# ProPrj_ArduinoUNoShield_ELE795_2026-08-0.net
KiCad netlist of a schematic drawn in EasyEDA Pro
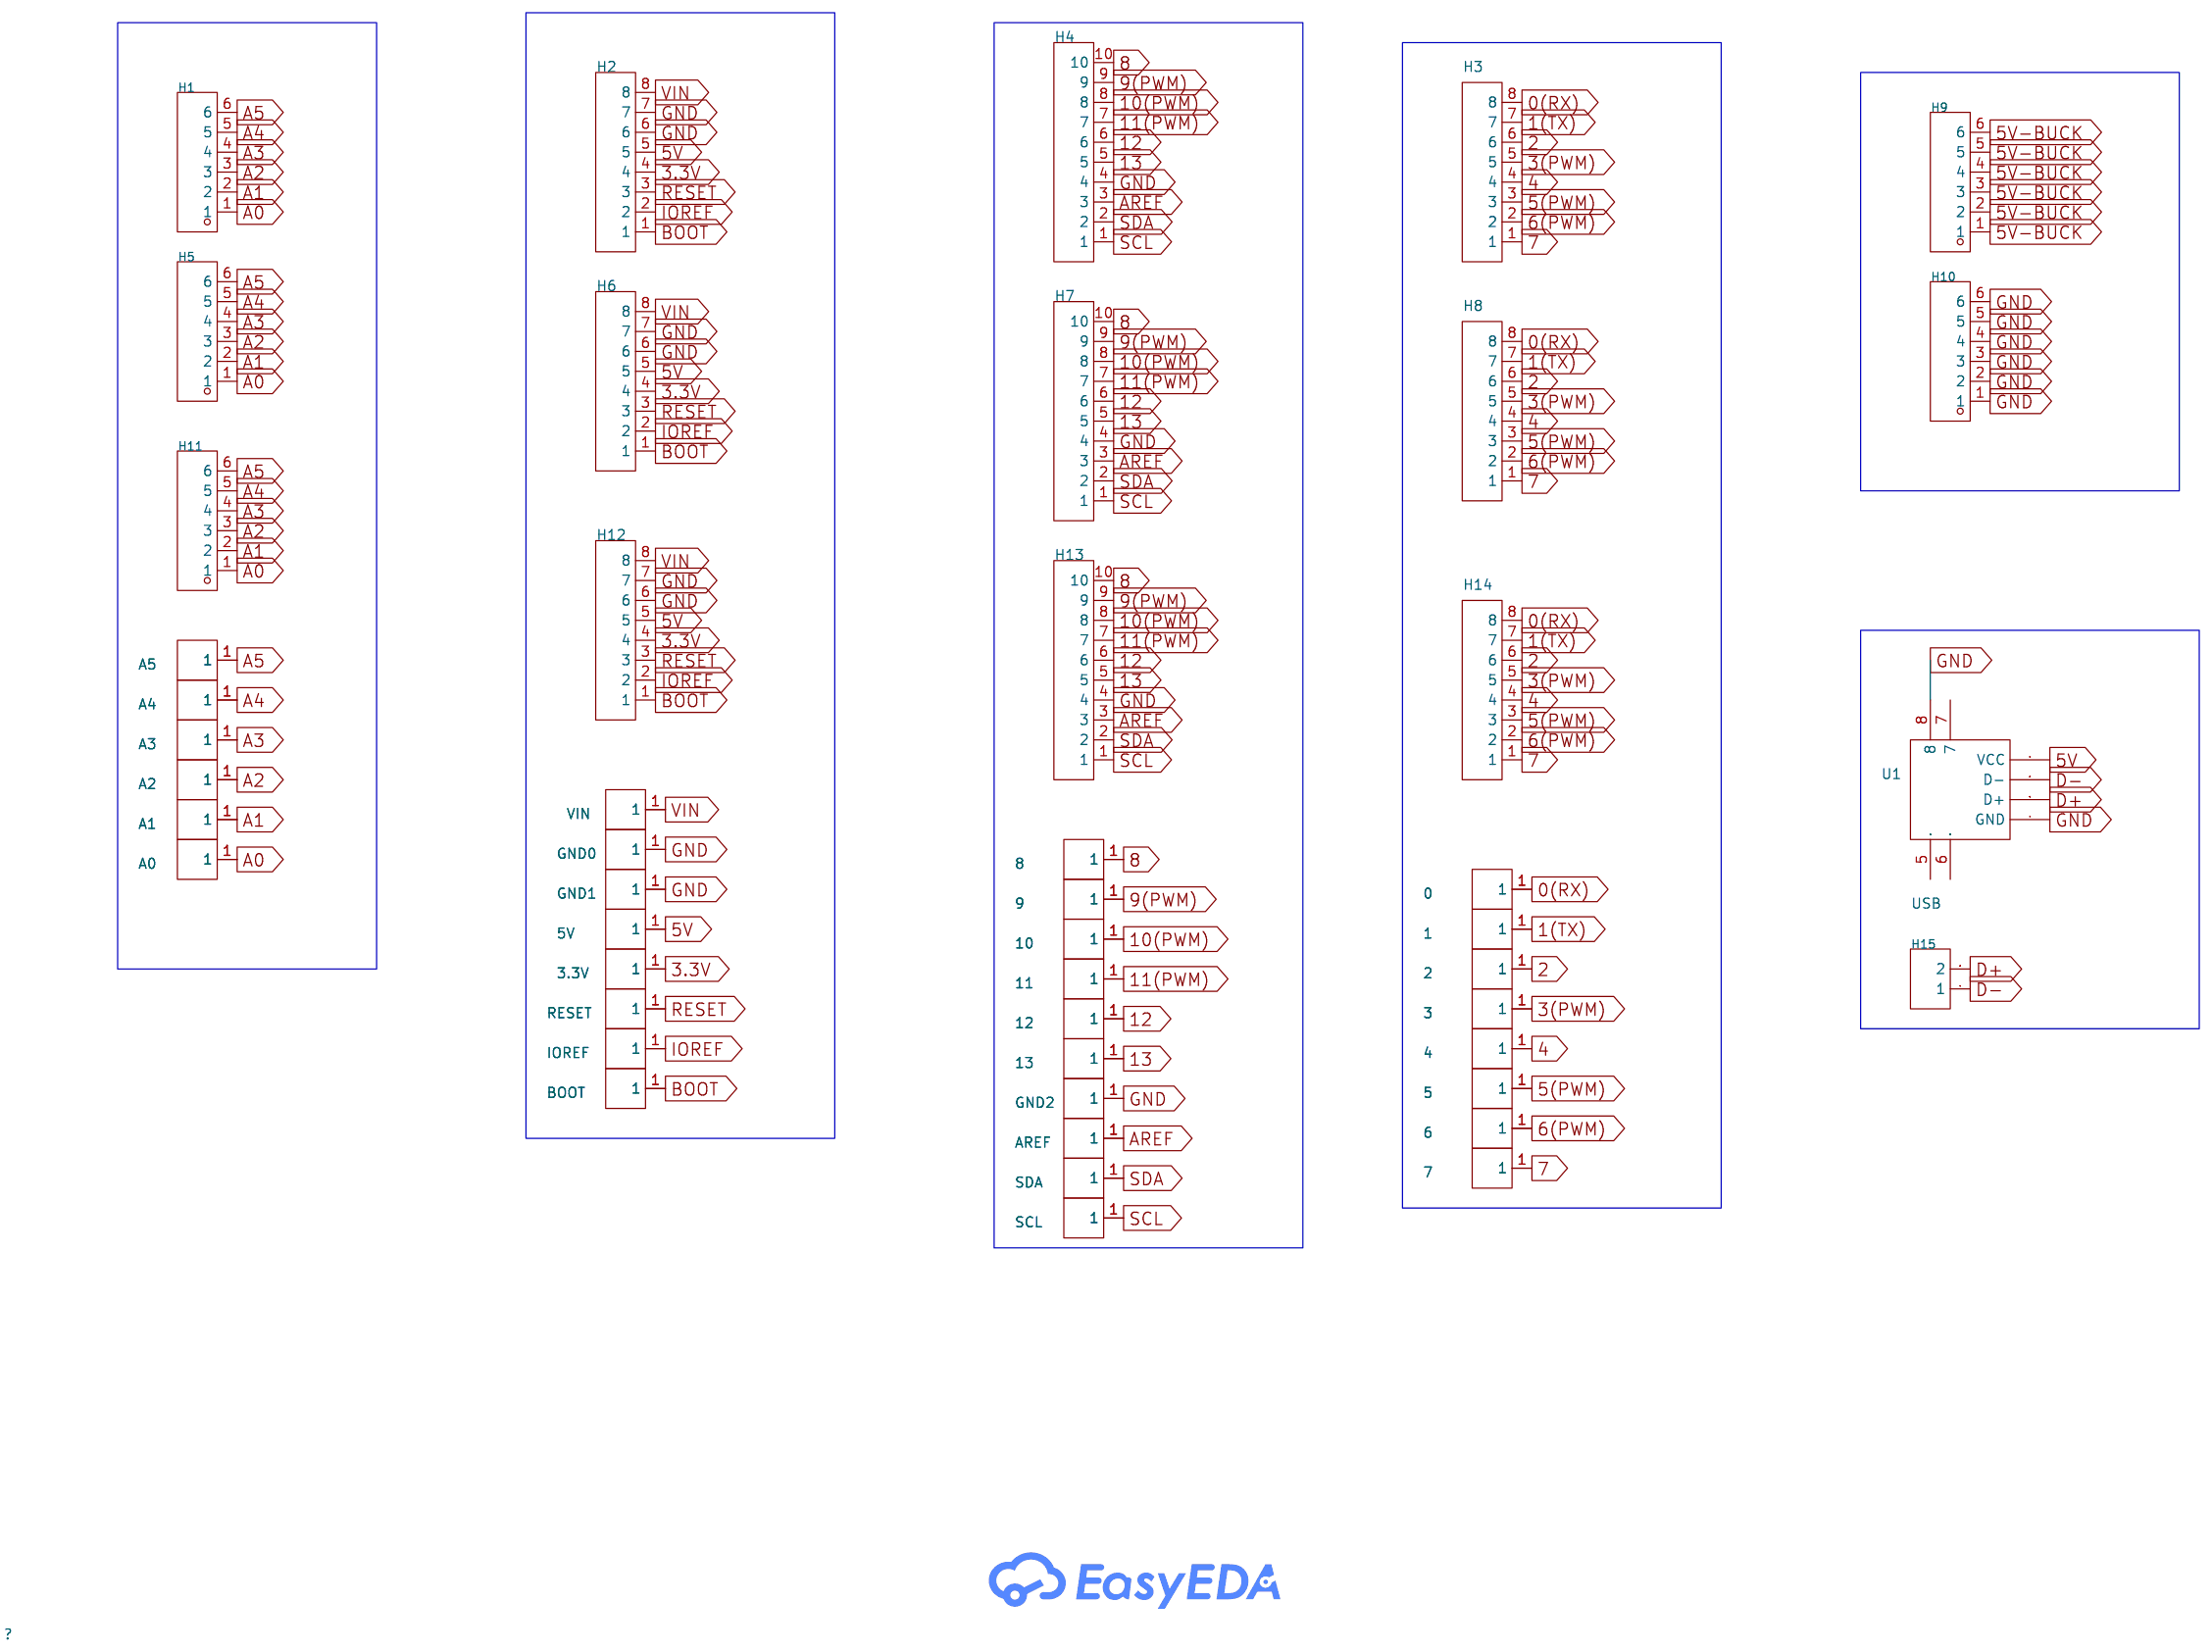
[diagram p0: schematic sheet]

(export (version "E")
  (design (tool "Eeschema 10.0.6"))
  (components
    (comp (ref "0")
      (value "5017")
      (footprint "easyedapro:CONN-SMD_5017")
      (libsource (lib "easyedapro") (part "5017_C9900015874"))
    )
    (comp (ref "1")
      (value "5017")
      (footprint "easyedapro:CONN-SMD_5017")
      (libsource (lib "easyedapro") (part "5017_C9900015874"))
    )
    (comp (ref "2")
      (value "5017")
      (footprint "easyedapro:CONN-SMD_5017")
      (libsource (lib "easyedapro") (part "5017_C9900015874"))
    )
    (comp (ref "3")
      (value "5017")
      (footprint "easyedapro:CONN-SMD_5017")
      (libsource (lib "easyedapro") (part "5017_C9900015874"))
    )
    (comp (ref "3.3V")
      (value "5017")
      (footprint "easyedapro:CONN-SMD_5017")
      (libsource (lib "easyedapro") (part "5017_C9900015874"))
    )
    (comp (ref "4")
      (value "5017")
      (footprint "easyedapro:CONN-SMD_5017")
      (libsource (lib "easyedapro") (part "5017_C9900015874"))
    )
    (comp (ref "5")
      (value "5017")
      (footprint "easyedapro:CONN-SMD_5017")
      (libsource (lib "easyedapro") (part "5017_C9900015874"))
    )
    (comp (ref "5V")
      (value "5017")
      (footprint "easyedapro:CONN-SMD_5017")
      (libsource (lib "easyedapro") (part "5017_C9900015874"))
    )
    (comp (ref "6")
      (value "5017")
      (footprint "easyedapro:CONN-SMD_5017")
      (libsource (lib "easyedapro") (part "5017_C9900015874"))
    )
    (comp (ref "7")
      (value "5017")
      (footprint "easyedapro:CONN-SMD_5017")
      (libsource (lib "easyedapro") (part "5017_C9900015874"))
    )
    (comp (ref "8")
      (value "5017")
      (footprint "easyedapro:CONN-SMD_5017")
      (libsource (lib "easyedapro") (part "5017_C9900015874"))
    )
    (comp (ref "9")
      (value "5017")
      (footprint "easyedapro:CONN-SMD_5017")
      (libsource (lib "easyedapro") (part "5017_C9900015874"))
    )
    (comp (ref "10")
      (value "5017")
      (footprint "easyedapro:CONN-SMD_5017")
      (libsource (lib "easyedapro") (part "5017_C9900015874"))
    )
    (comp (ref "11")
      (value "5017")
      (footprint "easyedapro:CONN-SMD_5017")
      (libsource (lib "easyedapro") (part "5017_C9900015874"))
    )
    (comp (ref "12")
      (value "5017")
      (footprint "easyedapro:CONN-SMD_5017")
      (libsource (lib "easyedapro") (part "5017_C9900015874"))
    )
    (comp (ref "13")
      (value "5017")
      (footprint "easyedapro:CONN-SMD_5017")
      (libsource (lib "easyedapro") (part "5017_C9900015874"))
    )
    (comp (ref "A0")
      (value "5017")
      (footprint "easyedapro:CONN-SMD_5017")
      (libsource (lib "easyedapro") (part "5017_C9900015874"))
    )
    (comp (ref "A1")
      (value "5017")
      (footprint "easyedapro:CONN-SMD_5017")
      (libsource (lib "easyedapro") (part "5017_C9900015874"))
    )
    (comp (ref "A2")
      (value "5017")
      (footprint "easyedapro:CONN-SMD_5017")
      (libsource (lib "easyedapro") (part "5017_C9900015874"))
    )
    (comp (ref "A3")
      (value "5017")
      (footprint "easyedapro:CONN-SMD_5017")
      (libsource (lib "easyedapro") (part "5017_C9900015874"))
    )
    (comp (ref "A4")
      (value "5017")
      (footprint "easyedapro:CONN-SMD_5017")
      (libsource (lib "easyedapro") (part "5017_C9900015874"))
    )
    (comp (ref "A5")
      (value "5017")
      (footprint "easyedapro:CONN-SMD_5017")
      (libsource (lib "easyedapro") (part "5017_C9900015874"))
    )
    (comp (ref "AREF")
      (value "5017")
      (footprint "easyedapro:CONN-SMD_5017")
      (libsource (lib "easyedapro") (part "5017_C9900015874"))
    )
    (comp (ref "BOOT")
      (value "5017")
      (footprint "easyedapro:CONN-SMD_5017")
      (libsource (lib "easyedapro") (part "5017_C9900015874"))
    )
    (comp (ref "GND0")
      (value "5017")
      (footprint "easyedapro:CONN-SMD_5017")
      (libsource (lib "easyedapro") (part "5017_C9900015874"))
    )
    (comp (ref "GND1")
      (value "5017")
      (footprint "easyedapro:CONN-SMD_5017")
      (libsource (lib "easyedapro") (part "5017_C9900015874"))
    )
    (comp (ref "GND2")
      (value "5017")
      (footprint "easyedapro:CONN-SMD_5017")
      (libsource (lib "easyedapro") (part "5017_C9900015874"))
    )
    (comp (ref "H1")
      (value "~")
      (footprint "easyedapro:HDR-TH_6P-P2.54-V-F")
      (libsource (lib "easyedapro") (part "Header-Female-2.54_1x6"))
    )
    (comp (ref "H2")
      (value "~")
      (footprint "easyedapro:HDR-TH_8P-P2.54-V-F-1")
      (libsource (lib "easyedapro") (part "Header-Female-2.54_1x8"))
    )
    (comp (ref "H3")
      (value "~")
      (footprint "easyedapro:HDR-TH_8P-P2.54-V-F-1")
      (libsource (lib "easyedapro") (part "Header-Female-2.54_1x8"))
    )
    (comp (ref "H4")
      (value "~")
      (footprint "easyedapro:HDR-TH_10P-P2.54-V-F")
      (libsource (lib "easyedapro") (part "X5511FV-10-C70D30-1000"))
    )
    (comp (ref "H5")
      (value "~")
      (footprint "easyedapro:HDR-TH_6P-P2.54-V-F")
      (libsource (lib "easyedapro") (part "Header-Female-2.54_1x6"))
    )
    (comp (ref "H6")
      (value "~")
      (footprint "easyedapro:HDR-TH_8P-P2.54-V-F-1")
      (libsource (lib "easyedapro") (part "Header-Female-2.54_1x8"))
    )
    (comp (ref "H7")
      (value "~")
      (footprint "easyedapro:HDR-TH_10P-P2.54-V-F")
      (libsource (lib "easyedapro") (part "X5511FV-10-C70D30-1000"))
    )
    (comp (ref "H8")
      (value "~")
      (footprint "easyedapro:HDR-TH_8P-P2.54-V-F-1")
      (libsource (lib "easyedapro") (part "Header-Female-2.54_1x8"))
    )
    (comp (ref "H9")
      (value "~")
      (footprint "easyedapro:HDR-TH_6P-P2.54-V-F")
      (libsource (lib "easyedapro") (part "Header-Female-2.54_1x6"))
    )
    (comp (ref "H10")
      (value "~")
      (footprint "easyedapro:HDR-TH_6P-P2.54-V-F")
      (libsource (lib "easyedapro") (part "Header-Female-2.54_1x6"))
    )
    (comp (ref "H11")
      (value "~")
      (footprint "easyedapro:HDR-TH_6P-P2.54-V-F")
      (libsource (lib "easyedapro") (part "Header-Female-2.54_1x6"))
    )
    (comp (ref "H12")
      (value "~")
      (footprint "easyedapro:HDR-TH_8P-P2.54-V-F-1")
      (libsource (lib "easyedapro") (part "Header-Female-2.54_1x8"))
    )
    (comp (ref "H13")
      (value "~")
      (footprint "easyedapro:HDR-TH_10P-P2.54-V-F")
      (libsource (lib "easyedapro") (part "X5511FV-10-C70D30-1000"))
    )
    (comp (ref "H14")
      (value "~")
      (footprint "easyedapro:HDR-TH_8P-P2.54-V-F-1")
      (libsource (lib "easyedapro") (part "Header-Female-2.54_1x8"))
    )
    (comp (ref "H15")
      (value "~")
      (footprint "easyedapro:HDR-TH_2P-P2.54-V-F")
      (libsource (lib "easyedapro") (part "Header-Female-2.54_1x2"))
    )
    (comp (ref "IOREF")
      (value "5017")
      (footprint "easyedapro:CONN-SMD_5017")
      (libsource (lib "easyedapro") (part "5017_C9900015874"))
    )
    (comp (ref "RESET")
      (value "5017")
      (footprint "easyedapro:CONN-SMD_5017")
      (libsource (lib "easyedapro") (part "5017_C9900015874"))
    )
    (comp (ref "SCL")
      (value "5017")
      (footprint "easyedapro:CONN-SMD_5017")
      (libsource (lib "easyedapro") (part "5017_C9900015874"))
    )
    (comp (ref "SDA")
      (value "5017")
      (footprint "easyedapro:CONN-SMD_5017")
      (libsource (lib "easyedapro") (part "5017_C9900015874"))
    )
    (comp (ref "U1")
      (value "USB")
      (footprint "easyedapro:USB-SMD_USB_1")
      (libsource (lib "easyedapro") (part "USB"))
    )
    (comp (ref "VIN")
      (value "5017")
      (footprint "easyedapro:CONN-SMD_5017")
      (libsource (lib "easyedapro") (part "5017_C9900015874"))
    )
  )
  (nets
    (net (code "1") (name "0(RX)") (class "Default")
      (node (ref "0") (pin "1") (pinfunction "1_1") (pintype "unspecified"))
      (node (ref "H14") (pin "8") (pinfunction "8_8") (pintype "unspecified"))
      (node (ref "H3") (pin "8") (pinfunction "8_8") (pintype "unspecified"))
      (node (ref "H8") (pin "8") (pinfunction "8_8") (pintype "unspecified"))
    )
    (net (code "2") (name "1(TX)") (class "Default")
      (node (ref "1") (pin "1") (pinfunction "1_1") (pintype "unspecified"))
      (node (ref "H14") (pin "7") (pinfunction "7_7") (pintype "unspecified"))
      (node (ref "H3") (pin "7") (pinfunction "7_7") (pintype "unspecified"))
      (node (ref "H8") (pin "7") (pinfunction "7_7") (pintype "unspecified"))
    )
    (net (code "3") (name "2") (class "Default")
      (node (ref "2") (pin "1") (pinfunction "1_1") (pintype "unspecified"))
      (node (ref "H14") (pin "6") (pinfunction "6_6") (pintype "unspecified"))
      (node (ref "H3") (pin "6") (pinfunction "6_6") (pintype "unspecified"))
      (node (ref "H8") (pin "6") (pinfunction "6_6") (pintype "unspecified"))
    )
    (net (code "4") (name "3(PWM)") (class "Default")
      (node (ref "3") (pin "1") (pinfunction "1_1") (pintype "unspecified"))
      (node (ref "H14") (pin "5") (pinfunction "5_5") (pintype "unspecified"))
      (node (ref "H3") (pin "5") (pinfunction "5_5") (pintype "unspecified"))
      (node (ref "H8") (pin "5") (pinfunction "5_5") (pintype "unspecified"))
    )
    (net (code "5") (name "3.3V") (class "Default")
      (node (ref "3.3V") (pin "1") (pinfunction "1_1") (pintype "unspecified"))
      (node (ref "H12") (pin "4") (pinfunction "4_4") (pintype "unspecified"))
      (node (ref "H2") (pin "4") (pinfunction "4_4") (pintype "unspecified"))
      (node (ref "H6") (pin "4") (pinfunction "4_4") (pintype "unspecified"))
    )
    (net (code "6") (name "4") (class "Default")
      (node (ref "4") (pin "1") (pinfunction "1_1") (pintype "unspecified"))
      (node (ref "H14") (pin "4") (pinfunction "4_4") (pintype "unspecified"))
      (node (ref "H3") (pin "4") (pinfunction "4_4") (pintype "unspecified"))
      (node (ref "H8") (pin "4") (pinfunction "4_4") (pintype "unspecified"))
    )
    (net (code "7") (name "5(PWM)") (class "Default")
      (node (ref "5") (pin "1") (pinfunction "1_1") (pintype "unspecified"))
      (node (ref "H14") (pin "3") (pinfunction "3_3") (pintype "unspecified"))
      (node (ref "H3") (pin "3") (pinfunction "3_3") (pintype "unspecified"))
      (node (ref "H8") (pin "3") (pinfunction "3_3") (pintype "unspecified"))
    )
    (net (code "8") (name "5V") (class "Default")
      (node (ref "5V") (pin "1") (pinfunction "1_1") (pintype "unspecified"))
      (node (ref "H12") (pin "5") (pinfunction "5_5") (pintype "unspecified"))
      (node (ref "H2") (pin "5") (pinfunction "5_5") (pintype "unspecified"))
      (node (ref "H6") (pin "5") (pinfunction "5_5") (pintype "unspecified"))
      (node (ref "U1") (pin "1") (pinfunction "VCC_1") (pintype "input"))
    )
    (net (code "9") (name "5V-BUCK") (class "Default")
      (node (ref "H9") (pin "1") (pinfunction "1_1") (pintype "input"))
      (node (ref "H9") (pin "2") (pinfunction "2_2") (pintype "input"))
      (node (ref "H9") (pin "3") (pinfunction "3_3") (pintype "input"))
      (node (ref "H9") (pin "4") (pinfunction "4_4") (pintype "input"))
      (node (ref "H9") (pin "5") (pinfunction "5_5") (pintype "input"))
      (node (ref "H9") (pin "6") (pinfunction "6_6") (pintype "input"))
    )
    (net (code "10") (name "6(PWM)") (class "Default")
      (node (ref "6") (pin "1") (pinfunction "1_1") (pintype "unspecified"))
      (node (ref "H14") (pin "2") (pinfunction "2_2") (pintype "unspecified"))
      (node (ref "H3") (pin "2") (pinfunction "2_2") (pintype "unspecified"))
      (node (ref "H8") (pin "2") (pinfunction "2_2") (pintype "unspecified"))
    )
    (net (code "11") (name "7") (class "Default")
      (node (ref "7") (pin "1") (pinfunction "1_1") (pintype "unspecified"))
      (node (ref "H14") (pin "1") (pinfunction "1_1") (pintype "unspecified"))
      (node (ref "H3") (pin "1") (pinfunction "1_1") (pintype "unspecified"))
      (node (ref "H8") (pin "1") (pinfunction "1_1") (pintype "unspecified"))
    )
    (net (code "12") (name "8") (class "Default")
      (node (ref "8") (pin "1") (pinfunction "1_1") (pintype "unspecified"))
      (node (ref "H13") (pin "10") (pinfunction "10_10") (pintype "unspecified"))
      (node (ref "H4") (pin "10") (pinfunction "10_10") (pintype "unspecified"))
      (node (ref "H7") (pin "10") (pinfunction "10_10") (pintype "unspecified"))
    )
    (net (code "13") (name "9(PWM)") (class "Default")
      (node (ref "9") (pin "1") (pinfunction "1_1") (pintype "unspecified"))
      (node (ref "H13") (pin "9") (pinfunction "9_9") (pintype "unspecified"))
      (node (ref "H4") (pin "9") (pinfunction "9_9") (pintype "unspecified"))
      (node (ref "H7") (pin "9") (pinfunction "9_9") (pintype "unspecified"))
    )
    (net (code "14") (name "10(PWM)") (class "Default")
      (node (ref "10") (pin "1") (pinfunction "1_1") (pintype "unspecified"))
      (node (ref "H13") (pin "8") (pinfunction "8_8") (pintype "unspecified"))
      (node (ref "H4") (pin "8") (pinfunction "8_8") (pintype "unspecified"))
      (node (ref "H7") (pin "8") (pinfunction "8_8") (pintype "unspecified"))
    )
    (net (code "15") (name "11(PWM)") (class "Default")
      (node (ref "11") (pin "1") (pinfunction "1_1") (pintype "unspecified"))
      (node (ref "H13") (pin "7") (pinfunction "7_7") (pintype "unspecified"))
      (node (ref "H4") (pin "7") (pinfunction "7_7") (pintype "unspecified"))
      (node (ref "H7") (pin "7") (pinfunction "7_7") (pintype "unspecified"))
    )
    (net (code "16") (name "12") (class "Default")
      (node (ref "12") (pin "1") (pinfunction "1_1") (pintype "unspecified"))
      (node (ref "H13") (pin "6") (pinfunction "6_6") (pintype "unspecified"))
      (node (ref "H4") (pin "6") (pinfunction "6_6") (pintype "unspecified"))
      (node (ref "H7") (pin "6") (pinfunction "6_6") (pintype "unspecified"))
    )
    (net (code "17") (name "13") (class "Default")
      (node (ref "13") (pin "1") (pinfunction "1_1") (pintype "unspecified"))
      (node (ref "H13") (pin "5") (pinfunction "5_5") (pintype "unspecified"))
      (node (ref "H4") (pin "5") (pinfunction "5_5") (pintype "unspecified"))
      (node (ref "H7") (pin "5") (pinfunction "5_5") (pintype "unspecified"))
    )
    (net (code "18") (name "A0") (class "Default")
      (node (ref "A0") (pin "1") (pinfunction "1_1") (pintype "unspecified"))
      (node (ref "H1") (pin "1") (pinfunction "1_1") (pintype "input"))
      (node (ref "H11") (pin "1") (pinfunction "1_1") (pintype "input"))
      (node (ref "H5") (pin "1") (pinfunction "1_1") (pintype "input"))
    )
    (net (code "19") (name "A1") (class "Default")
      (node (ref "A1") (pin "1") (pinfunction "1_1") (pintype "unspecified"))
      (node (ref "H1") (pin "2") (pinfunction "2_2") (pintype "input"))
      (node (ref "H11") (pin "2") (pinfunction "2_2") (pintype "input"))
      (node (ref "H5") (pin "2") (pinfunction "2_2") (pintype "input"))
    )
    (net (code "20") (name "A2") (class "Default")
      (node (ref "A2") (pin "1") (pinfunction "1_1") (pintype "unspecified"))
      (node (ref "H1") (pin "3") (pinfunction "3_3") (pintype "input"))
      (node (ref "H11") (pin "3") (pinfunction "3_3") (pintype "input"))
      (node (ref "H5") (pin "3") (pinfunction "3_3") (pintype "input"))
    )
    (net (code "21") (name "A3") (class "Default")
      (node (ref "A3") (pin "1") (pinfunction "1_1") (pintype "unspecified"))
      (node (ref "H1") (pin "4") (pinfunction "4_4") (pintype "input"))
      (node (ref "H11") (pin "4") (pinfunction "4_4") (pintype "input"))
      (node (ref "H5") (pin "4") (pinfunction "4_4") (pintype "input"))
    )
    (net (code "22") (name "A4") (class "Default")
      (node (ref "A4") (pin "1") (pinfunction "1_1") (pintype "unspecified"))
      (node (ref "H1") (pin "5") (pinfunction "5_5") (pintype "input"))
      (node (ref "H11") (pin "5") (pinfunction "5_5") (pintype "input"))
      (node (ref "H5") (pin "5") (pinfunction "5_5") (pintype "input"))
    )
    (net (code "23") (name "A5") (class "Default")
      (node (ref "A5") (pin "1") (pinfunction "1_1") (pintype "unspecified"))
      (node (ref "H1") (pin "6") (pinfunction "6_6") (pintype "input"))
      (node (ref "H11") (pin "6") (pinfunction "6_6") (pintype "input"))
      (node (ref "H5") (pin "6") (pinfunction "6_6") (pintype "input"))
    )
    (net (code "24") (name "AREF") (class "Default")
      (node (ref "AREF") (pin "1") (pinfunction "1_1") (pintype "unspecified"))
      (node (ref "H13") (pin "3") (pinfunction "3_3") (pintype "unspecified"))
      (node (ref "H4") (pin "3") (pinfunction "3_3") (pintype "unspecified"))
      (node (ref "H7") (pin "3") (pinfunction "3_3") (pintype "unspecified"))
    )
    (net (code "25") (name "BOOT") (class "Default")
      (node (ref "BOOT") (pin "1") (pinfunction "1_1") (pintype "unspecified"))
      (node (ref "H12") (pin "1") (pinfunction "1_1") (pintype "unspecified"))
      (node (ref "H2") (pin "1") (pinfunction "1_1") (pintype "unspecified"))
      (node (ref "H6") (pin "1") (pinfunction "1_1") (pintype "unspecified"))
    )
    (net (code "26") (name "D+") (class "Default")
      (node (ref "H15") (pin "2") (pinfunction "2_2") (pintype "input"))
      (node (ref "U1") (pin "3") (pinfunction "D+_3") (pintype "input"))
    )
    (net (code "27") (name "D-") (class "Default")
      (node (ref "H15") (pin "1") (pinfunction "1_1") (pintype "input"))
      (node (ref "U1") (pin "2") (pinfunction "D-_2") (pintype "input"))
    )
    (net (code "28") (name "GND") (class "Default")
      (node (ref "GND0") (pin "1") (pinfunction "1_1") (pintype "unspecified"))
      (node (ref "GND1") (pin "1") (pinfunction "1_1") (pintype "unspecified"))
      (node (ref "GND2") (pin "1") (pinfunction "1_1") (pintype "unspecified"))
      (node (ref "H10") (pin "1") (pinfunction "1_1") (pintype "input"))
      (node (ref "H10") (pin "2") (pinfunction "2_2") (pintype "input"))
      (node (ref "H10") (pin "3") (pinfunction "3_3") (pintype "input"))
      (node (ref "H10") (pin "4") (pinfunction "4_4") (pintype "input"))
      (node (ref "H10") (pin "5") (pinfunction "5_5") (pintype "input"))
      (node (ref "H10") (pin "6") (pinfunction "6_6") (pintype "input"))
      (node (ref "H12") (pin "6") (pinfunction "6_6") (pintype "unspecified"))
      (node (ref "H12") (pin "7") (pinfunction "7_7") (pintype "unspecified"))
      (node (ref "H13") (pin "4") (pinfunction "4_4") (pintype "unspecified"))
      (node (ref "H2") (pin "6") (pinfunction "6_6") (pintype "unspecified"))
      (node (ref "H2") (pin "7") (pinfunction "7_7") (pintype "unspecified"))
      (node (ref "H4") (pin "4") (pinfunction "4_4") (pintype "unspecified"))
      (node (ref "H6") (pin "6") (pinfunction "6_6") (pintype "unspecified"))
      (node (ref "H6") (pin "7") (pinfunction "7_7") (pintype "unspecified"))
      (node (ref "H7") (pin "4") (pinfunction "4_4") (pintype "unspecified"))
      (node (ref "U1") (pin "4") (pinfunction "GND_4") (pintype "input"))
      (node (ref "U1") (pin "8") (pinfunction "8_8") (pintype "unspecified"))
    )
    (net (code "29") (name "IOREF") (class "Default")
      (node (ref "H12") (pin "2") (pinfunction "2_2") (pintype "unspecified"))
      (node (ref "H2") (pin "2") (pinfunction "2_2") (pintype "unspecified"))
      (node (ref "H6") (pin "2") (pinfunction "2_2") (pintype "unspecified"))
      (node (ref "IOREF") (pin "1") (pinfunction "1_1") (pintype "unspecified"))
    )
    (net (code "30") (name "RESET") (class "Default")
      (node (ref "H12") (pin "3") (pinfunction "3_3") (pintype "unspecified"))
      (node (ref "H2") (pin "3") (pinfunction "3_3") (pintype "unspecified"))
      (node (ref "H6") (pin "3") (pinfunction "3_3") (pintype "unspecified"))
      (node (ref "RESET") (pin "1") (pinfunction "1_1") (pintype "unspecified"))
    )
    (net (code "31") (name "SCL") (class "Default")
      (node (ref "H13") (pin "1") (pinfunction "1_1") (pintype "unspecified"))
      (node (ref "H4") (pin "1") (pinfunction "1_1") (pintype "unspecified"))
      (node (ref "H7") (pin "1") (pinfunction "1_1") (pintype "unspecified"))
      (node (ref "SCL") (pin "1") (pinfunction "1_1") (pintype "unspecified"))
    )
    (net (code "32") (name "SDA") (class "Default")
      (node (ref "H13") (pin "2") (pinfunction "2_2") (pintype "unspecified"))
      (node (ref "H4") (pin "2") (pinfunction "2_2") (pintype "unspecified"))
      (node (ref "H7") (pin "2") (pinfunction "2_2") (pintype "unspecified"))
      (node (ref "SDA") (pin "1") (pinfunction "1_1") (pintype "unspecified"))
    )
    (net (code "33") (name "VIN") (class "Default")
      (node (ref "H12") (pin "8") (pinfunction "8_8") (pintype "unspecified"))
      (node (ref "H2") (pin "8") (pinfunction "8_8") (pintype "unspecified"))
      (node (ref "H6") (pin "8") (pinfunction "8_8") (pintype "unspecified"))
      (node (ref "VIN") (pin "1") (pinfunction "1_1") (pintype "unspecified"))
    )
    (net (code "34") (name "unconnected-(U1-Pad7)") (class "Default")
      (node (ref "U1") (pin "7") (pinfunction "7_7") (pintype "unspecified"))
    )
    (net (code "35") (name "unconnected-(U1-SH1-Pad5)") (class "Default")
      (node (ref "U1") (pin "5") (pinfunction "SH1_5") (pintype "unspecified"))
    )
    (net (code "36") (name "unconnected-(U1-SH2-Pad6)") (class "Default")
      (node (ref "U1") (pin "6") (pinfunction "SH2_6") (pintype "unspecified"))
    )
  )
)
